# WirelessPowerRxExtensionBoard.net
KiCad netlist of a schematic drawn in EAGLE
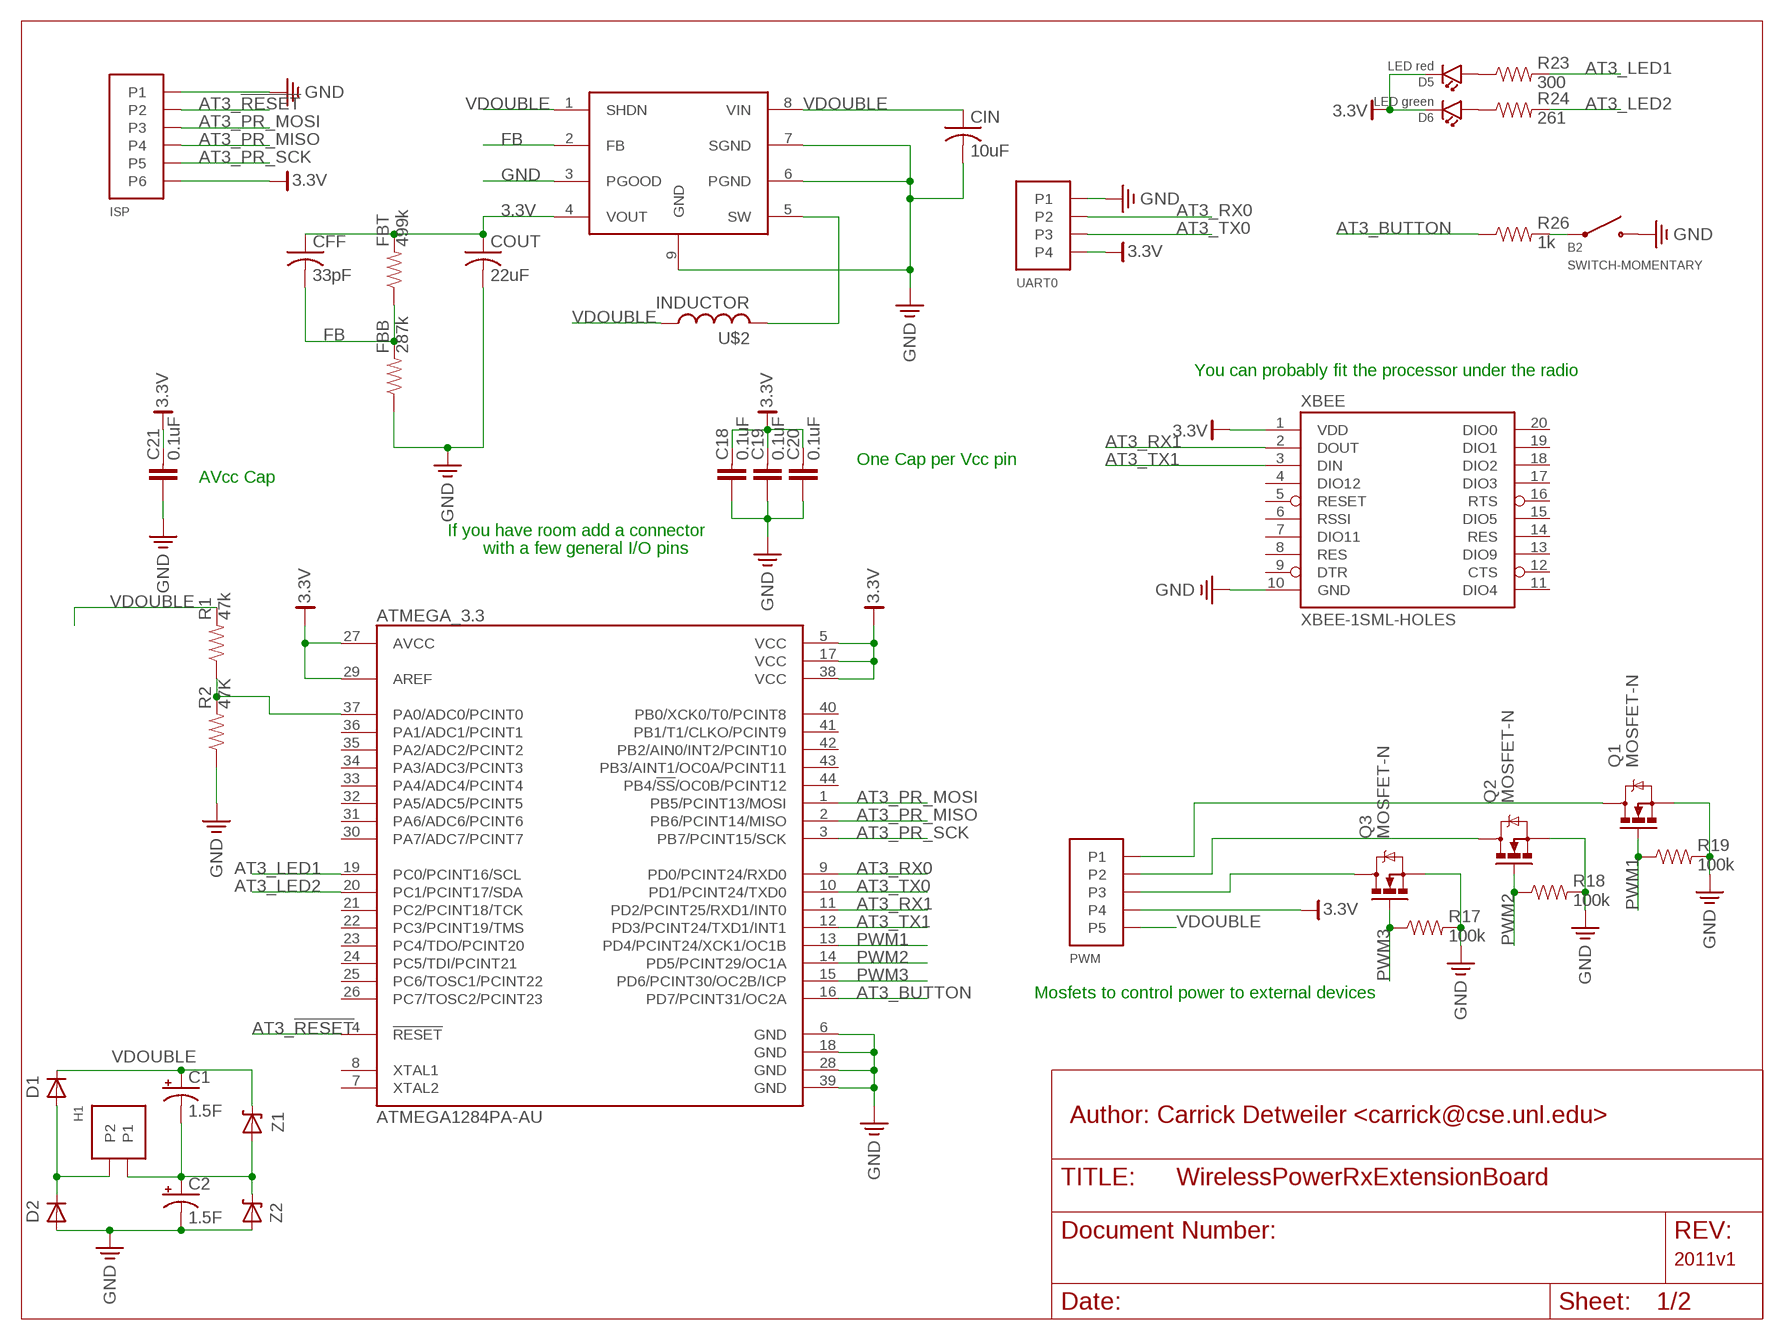
[diagram p0: schematic, sheet 1]
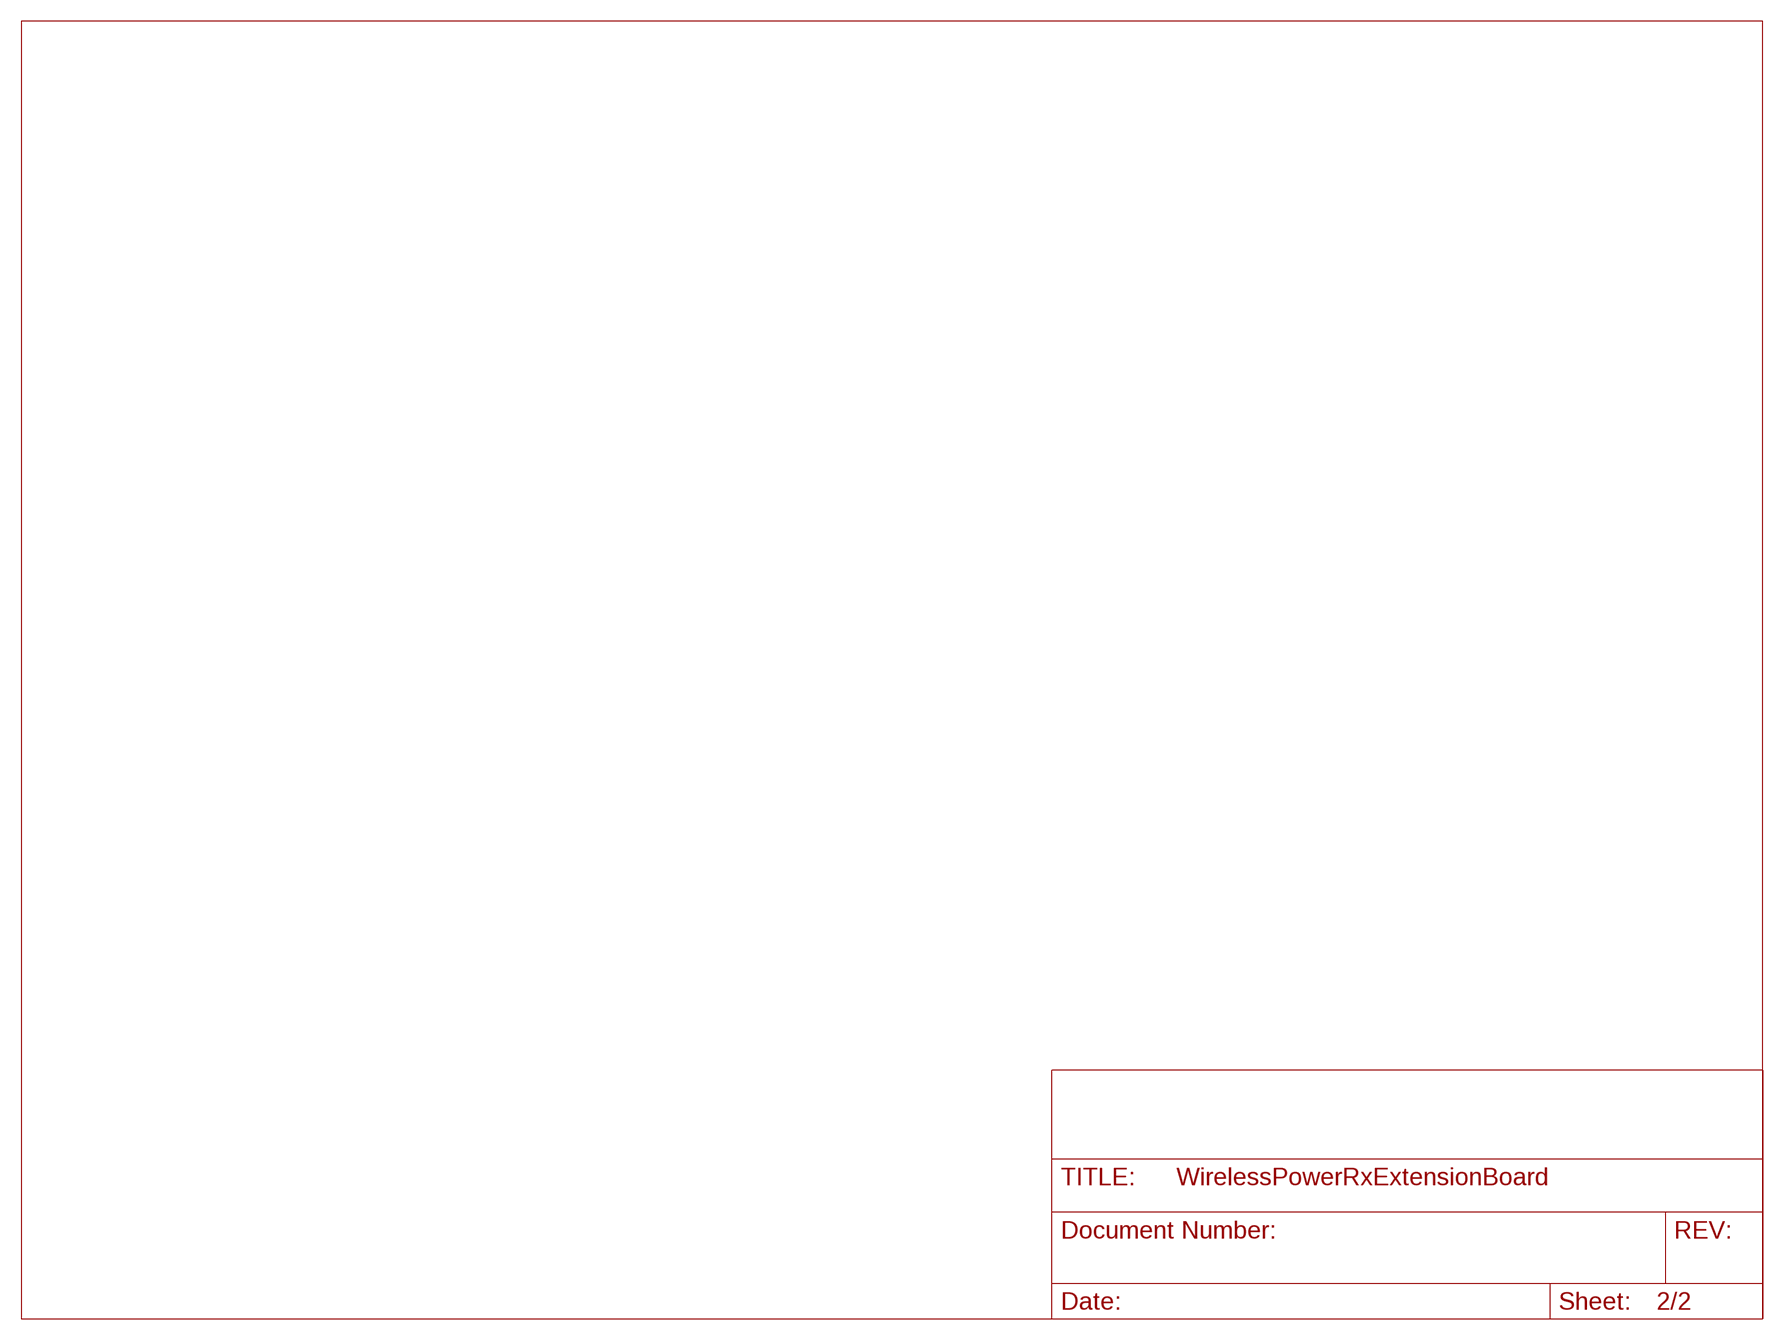
[diagram p1: schematic, sheet 2]

(export (version "E")
  (design (tool "Eeschema 10.0.6"))
  (components
    (comp (ref "ATMEGA_3.3")
      (value "ATMEGA1284PA-AU")
      (footprint "eagle-import:AT_TQFP-44")
      (libsource (lib "eagle-import") (part "ATMEGA164PA-AU"))
    )
    (comp (ref "B2")
      (value "SWITCH-MOMENTARY")
      (footprint "eagle-import:SWITCH-MOMENTARY-PTS635-SMD")
      (libsource (lib "eagle-import") (part "SWITCH-MOMENTARY"))
    )
    (comp (ref "C1")
      (value "1.5F")
      (footprint "eagle-import:E5-10,5")
      (libsource (lib "eagle-import") (part "CPOL-USE5-10.5"))
    )
    (comp (ref "C2")
      (value "1.5F")
      (footprint "eagle-import:E5-10,5")
      (libsource (lib "eagle-import") (part "CPOL-USE5-10.5"))
    )
    (comp (ref "C18")
      (value "0.1uF")
      (footprint "eagle-import:C0603")
      (libsource (lib "eagle-import") (part "CAP0603"))
    )
    (comp (ref "C19")
      (value "0.1uF")
      (footprint "eagle-import:C0603")
      (libsource (lib "eagle-import") (part "CAP0603"))
    )
    (comp (ref "C20")
      (value "0.1uF")
      (footprint "eagle-import:C0603")
      (libsource (lib "eagle-import") (part "CAP0603"))
    )
    (comp (ref "C21")
      (value "0.1uF")
      (footprint "eagle-import:C0603")
      (libsource (lib "eagle-import") (part "CAP0603"))
    )
    (comp (ref "CFF")
      (value "33pF")
      (footprint "eagle-import:C0201")
      (libsource (lib "eagle-import") (part "C-USC0201"))
    )
    (comp (ref "CIN")
      (value "10uF")
      (footprint "eagle-import:C0805")
      (libsource (lib "eagle-import") (part "C-USC0805"))
    )
    (comp (ref "COUT")
      (value "22uF")
      (footprint "eagle-import:C0805")
      (libsource (lib "eagle-import") (part "C-USC0805"))
    )
    (comp (ref "D1")
      (value "DIODE")
      (footprint "eagle-import:DO-214AB")
      (libsource (lib "eagle-import") (part "DIODE"))
    )
    (comp (ref "D2")
      (value "DIODE")
      (footprint "eagle-import:DO-214AB")
      (libsource (lib "eagle-import") (part "DIODE"))
    )
    (comp (ref "D5")
      (value "LED red")
      (footprint "eagle-import:LED0603")
      (libsource (lib "eagle-import") (part "LED"))
    )
    (comp (ref "D6")
      (value "LED green")
      (footprint "eagle-import:LED0603")
      (libsource (lib "eagle-import") (part "LED"))
    )
    (comp (ref "FBB")
      (value "287k")
      (footprint "eagle-import:R0603")
      (libsource (lib "eagle-import") (part "carrick_RES0603"))
    )
    (comp (ref "FBT")
      (value "499k")
      (footprint "eagle-import:R0603")
      (libsource (lib "eagle-import") (part "carrick_RES0603"))
    )
    (comp (ref "H1")
      (value "DF3-2")
      (footprint "eagle-import:DF3-2")
      (libsource (lib "eagle-import") (part "DF3-2"))
    )
    (comp (ref "ISP")
      (value "DF3-6")
      (footprint "eagle-import:DF3-6")
      (libsource (lib "eagle-import") (part "DF3-6"))
    )
    (comp (ref "PWM")
      (value "DF3-5")
      (footprint "eagle-import:DF3-5")
      (libsource (lib "eagle-import") (part "DF3-5"))
    )
    (comp (ref "Q1")
      (value "MOSFET-N")
      (footprint "eagle-import:SOT-23")
      (libsource (lib "eagle-import") (part "MOSFET-N"))
    )
    (comp (ref "Q2")
      (value "MOSFET-N")
      (footprint "eagle-import:SOT-23")
      (libsource (lib "eagle-import") (part "MOSFET-N"))
    )
    (comp (ref "Q3")
      (value "MOSFET-N")
      (footprint "eagle-import:SOT-23")
      (libsource (lib "eagle-import") (part "MOSFET-N"))
    )
    (comp (ref "R1")
      (value "47k")
      (footprint "eagle-import:R0603")
      (libsource (lib "eagle-import") (part "carrick_RES0603"))
    )
    (comp (ref "R2")
      (value "47K")
      (footprint "eagle-import:R0603")
      (libsource (lib "eagle-import") (part "carrick_RES0603"))
    )
    (comp (ref "R17")
      (value "100k")
      (footprint "eagle-import:R0603")
      (libsource (lib "eagle-import") (part "carrick_RES0603"))
    )
    (comp (ref "R18")
      (value "100k")
      (footprint "eagle-import:R0603")
      (libsource (lib "eagle-import") (part "carrick_RES0603"))
    )
    (comp (ref "R19")
      (value "100k")
      (footprint "eagle-import:R0603")
      (libsource (lib "eagle-import") (part "carrick_RES0603"))
    )
    (comp (ref "R23")
      (value "300")
      (footprint "eagle-import:R0603")
      (libsource (lib "eagle-import") (part "RES0603"))
    )
    (comp (ref "R24")
      (value "261")
      (footprint "eagle-import:R0603")
      (libsource (lib "eagle-import") (part "RES0603"))
    )
    (comp (ref "R26")
      (value "1k")
      (footprint "eagle-import:R0603")
      (libsource (lib "eagle-import") (part "RES0603"))
    )
    (comp (ref "U$1")
      (value "STEPUPCONVERTER")
      (footprint "eagle-import:LTC3528_LTC3528B")
      (libsource (lib "eagle-import") (part "STEPUPCONVERTER"))
    )
    (comp (ref "U$2")
      (value "INDUCTOR")
      (footprint "eagle-import:WE-TPC-M")
      (libsource (lib "eagle-import") (part "INDUCTOR"))
    )
    (comp (ref "UART0")
      (value "DF3-4")
      (footprint "eagle-import:DF3-4")
      (libsource (lib "eagle-import") (part "DF3-4"))
    )
    (comp (ref "XBEE")
      (value "XBEE-1SML-HOLES")
      (footprint "eagle-import:XBEE-SML-HOLES")
      (libsource (lib "eagle-import") (part "XBEE-1SML-HOLES"))
    )
    (comp (ref "Z1")
      (value "ZENERDIODE")
      (footprint "eagle-import:SOD-123")
      (libsource (lib "eagle-import") (part "ZENERDIODE"))
    )
    (comp (ref "Z2")
      (value "ZENERDIODE")
      (footprint "eagle-import:SOD-123")
      (libsource (lib "eagle-import") (part "ZENERDIODE"))
    )
  )
  (nets
    (net (code "1") (name "3.3V") (class "Default")
      (node (ref "ATMEGA_3.3") (pin "17") (pinfunction "VCC_17") (pintype "power_in"))
      (node (ref "ATMEGA_3.3") (pin "27") (pinfunction "AVCC_27") (pintype "power_in"))
      (node (ref "ATMEGA_3.3") (pin "29") (pinfunction "AREF_29") (pintype "passive"))
      (node (ref "ATMEGA_3.3") (pin "38") (pinfunction "VCC_38") (pintype "power_in"))
      (node (ref "ATMEGA_3.3") (pin "5") (pinfunction "VCC_5") (pintype "power_in"))
      (node (ref "C18") (pin "P$2") (pinfunction "P$2_P$2") (pintype "bidirectional"))
      (node (ref "C19") (pin "P$2") (pinfunction "P$2_P$2") (pintype "bidirectional"))
      (node (ref "C20") (pin "P$2") (pinfunction "P$2_P$2") (pintype "bidirectional"))
      (node (ref "C21") (pin "P$2") (pinfunction "P$2_P$2") (pintype "bidirectional"))
      (node (ref "CFF") (pin "1") (pinfunction "1_1") (pintype "passive"))
      (node (ref "COUT") (pin "1") (pinfunction "1_1") (pintype "passive"))
      (node (ref "D5") (pin "P$2") (pinfunction "P$2_P$2") (pintype "bidirectional"))
      (node (ref "D6") (pin "P$2") (pinfunction "P$2_P$2") (pintype "bidirectional"))
      (node (ref "FBT") (pin "P$2") (pinfunction "2_P$2") (pintype "passive"))
      (node (ref "ISP") (pin "P$6") (pinfunction "P6_P$6") (pintype "bidirectional"))
      (node (ref "PWM") (pin "P$4") (pinfunction "P4_P$4") (pintype "bidirectional"))
      (node (ref "U$1") (pin "4") (pinfunction "VOUT_4") (pintype "power_in"))
      (node (ref "UART0") (pin "P$4") (pinfunction "P4_P$4") (pintype "bidirectional"))
      (node (ref "XBEE") (pin "1") (pinfunction "VDD_1") (pintype "power_in"))
    )
    (net (code "2") (name "AT3_BUTTON") (class "Default")
      (node (ref "ATMEGA_3.3") (pin "16") (pinfunction "PD7/PCINT31/OC2A_16") (pintype "bidirectional"))
      (node (ref "R26") (pin "P$1") (pinfunction "1_P$1") (pintype "passive"))
    )
    (net (code "3") (name "AT3_LED1") (class "Default")
      (node (ref "ATMEGA_3.3") (pin "19") (pinfunction "PC0/PCINT16/SCL_19") (pintype "bidirectional"))
      (node (ref "R23") (pin "P$2") (pinfunction "2_P$2") (pintype "passive"))
    )
    (net (code "4") (name "AT3_LED2") (class "Default")
      (node (ref "ATMEGA_3.3") (pin "20") (pinfunction "PC1/PCINT17/SDA_20") (pintype "bidirectional"))
      (node (ref "R24") (pin "P$2") (pinfunction "2_P$2") (pintype "passive"))
    )
    (net (code "5") (name "AT3_PR_MISO") (class "Default")
      (node (ref "ATMEGA_3.3") (pin "2") (pinfunction "PB6/PCINT14/MISO_2") (pintype "bidirectional"))
      (node (ref "ISP") (pin "P$4") (pinfunction "P4_P$4") (pintype "bidirectional"))
    )
    (net (code "6") (name "AT3_PR_MOSI") (class "Default")
      (node (ref "ATMEGA_3.3") (pin "1") (pinfunction "PB5/PCINT13/MOSI_1") (pintype "bidirectional"))
      (node (ref "ISP") (pin "P$3") (pinfunction "P3_P$3") (pintype "bidirectional"))
    )
    (net (code "7") (name "AT3_PR_SCK") (class "Default")
      (node (ref "ATMEGA_3.3") (pin "3") (pinfunction "PB7/PCINT15/SCK_3") (pintype "bidirectional"))
      (node (ref "ISP") (pin "P$5") (pinfunction "P5_P$5") (pintype "bidirectional"))
    )
    (net (code "8") (name "AT3_RX0") (class "Default")
      (node (ref "ATMEGA_3.3") (pin "9") (pinfunction "PD0/PCINT24/RXD0_9") (pintype "bidirectional"))
      (node (ref "UART0") (pin "P$2") (pinfunction "P2_P$2") (pintype "bidirectional"))
    )
    (net (code "9") (name "AT3_RX1") (class "Default")
      (node (ref "ATMEGA_3.3") (pin "11") (pinfunction "PD2/PCINT25/RXD1/INT0_11") (pintype "bidirectional"))
      (node (ref "XBEE") (pin "2") (pinfunction "DOUT_2") (pintype "output"))
    )
    (net (code "10") (name "AT3_TX0") (class "Default")
      (node (ref "ATMEGA_3.3") (pin "10") (pinfunction "PD1/PCINT24/TXD0_10") (pintype "bidirectional"))
      (node (ref "UART0") (pin "P$3") (pinfunction "P3_P$3") (pintype "bidirectional"))
    )
    (net (code "11") (name "AT3_TX1") (class "Default")
      (node (ref "ATMEGA_3.3") (pin "12") (pinfunction "PD3/PCINT24/TXD1/INT1_12") (pintype "bidirectional"))
      (node (ref "XBEE") (pin "3") (pinfunction "DIN_3") (pintype "input"))
    )
    (net (code "12") (name "AT3_~{RESET}") (class "Default")
      (node (ref "ATMEGA_3.3") (pin "4") (pinfunction "~{RESET}_4") (pintype "input"))
      (node (ref "ISP") (pin "P$2") (pinfunction "P2_P$2") (pintype "bidirectional"))
    )
    (net (code "13") (name "FB") (class "Default")
      (node (ref "CFF") (pin "2") (pinfunction "2_2") (pintype "passive"))
      (node (ref "FBB") (pin "P$2") (pinfunction "2_P$2") (pintype "passive"))
      (node (ref "FBT") (pin "P$1") (pinfunction "1_P$1") (pintype "passive"))
      (node (ref "U$1") (pin "2") (pinfunction "FB_2") (pintype "bidirectional"))
    )
    (net (code "14") (name "GND") (class "Default")
      (node (ref "ATMEGA_3.3") (pin "18") (pinfunction "GND_18") (pintype "power_in"))
      (node (ref "ATMEGA_3.3") (pin "28") (pinfunction "GND_28") (pintype "power_in"))
      (node (ref "ATMEGA_3.3") (pin "39") (pinfunction "GND_39") (pintype "power_in"))
      (node (ref "ATMEGA_3.3") (pin "6") (pinfunction "GND_6") (pintype "power_in"))
      (node (ref "B2") (pin "P$2") (pinfunction "P$2_P$2") (pintype "bidirectional"))
      (node (ref "C18") (pin "P$1") (pinfunction "P$1_P$1") (pintype "bidirectional"))
      (node (ref "C19") (pin "P$1") (pinfunction "P$1_P$1") (pintype "bidirectional"))
      (node (ref "C2") (pin "-") (pinfunction "-_-") (pintype "passive"))
      (node (ref "C20") (pin "P$1") (pinfunction "P$1_P$1") (pintype "bidirectional"))
      (node (ref "C21") (pin "P$1") (pinfunction "P$1_P$1") (pintype "bidirectional"))
      (node (ref "CIN") (pin "2") (pinfunction "2_2") (pintype "passive"))
      (node (ref "COUT") (pin "2") (pinfunction "2_2") (pintype "passive"))
      (node (ref "D2") (pin "P$2") (pinfunction "A_P$2") (pintype "passive"))
      (node (ref "FBB") (pin "P$1") (pinfunction "1_P$1") (pintype "passive"))
      (node (ref "ISP") (pin "P$1") (pinfunction "P1_P$1") (pintype "bidirectional"))
      (node (ref "Q1") (pin "2") (pinfunction "S_2") (pintype "passive"))
      (node (ref "Q2") (pin "2") (pinfunction "S_2") (pintype "passive"))
      (node (ref "Q3") (pin "2") (pinfunction "S_2") (pintype "passive"))
      (node (ref "R17") (pin "P$2") (pinfunction "2_P$2") (pintype "passive"))
      (node (ref "R18") (pin "P$2") (pinfunction "2_P$2") (pintype "passive"))
      (node (ref "R19") (pin "P$2") (pinfunction "2_P$2") (pintype "passive"))
      (node (ref "R2") (pin "P$1") (pinfunction "1_P$1") (pintype "passive"))
      (node (ref "U$1") (pin "3") (pinfunction "PGOOD_3") (pintype "bidirectional"))
      (node (ref "U$1") (pin "6") (pinfunction "PGND_6") (pintype "bidirectional"))
      (node (ref "U$1") (pin "7") (pinfunction "SGND_7") (pintype "bidirectional"))
      (node (ref "U$1") (pin "9") (pinfunction "GND_9") (pintype "power_in"))
      (node (ref "UART0") (pin "P$1") (pinfunction "P1_P$1") (pintype "bidirectional"))
      (node (ref "XBEE") (pin "10") (pinfunction "GND_10") (pintype "power_in"))
      (node (ref "Z2") (pin "P$2") (pinfunction "A_P$2") (pintype "passive"))
    )
    (net (code "15") (name "Net-(ATMEGA_3.3-PA0{slash}ADC0{slash}PCINT0)") (class "Default")
      (node (ref "ATMEGA_3.3") (pin "37") (pinfunction "PA0/ADC0/PCINT0_37") (pintype "bidirectional"))
      (node (ref "R1") (pin "P$1") (pinfunction "1_P$1") (pintype "passive"))
      (node (ref "R2") (pin "P$2") (pinfunction "2_P$2") (pintype "passive"))
    )
    (net (code "16") (name "Net-(D1-A)") (class "Default")
      (node (ref "D1") (pin "P$2") (pinfunction "A_P$2") (pintype "passive"))
      (node (ref "D2") (pin "P$1") (pinfunction "C_P$1") (pintype "passive"))
      (node (ref "H1") (pin "P$2") (pinfunction "P2_P$2") (pintype "bidirectional"))
    )
    (net (code "17") (name "Net-(H1-P1)") (class "Default")
      (node (ref "C1") (pin "-") (pinfunction "-_-") (pintype "passive"))
      (node (ref "C2") (pin "+") (pinfunction "+_+") (pintype "passive"))
      (node (ref "H1") (pin "P$1") (pinfunction "P1_P$1") (pintype "bidirectional"))
      (node (ref "Z1") (pin "P$2") (pinfunction "A_P$2") (pintype "passive"))
      (node (ref "Z2") (pin "P$1") (pinfunction "C_P$1") (pintype "passive"))
    )
    (net (code "18") (name "Net-(PWM-P1)") (class "Default")
      (node (ref "PWM") (pin "P$1") (pinfunction "P1_P$1") (pintype "bidirectional"))
      (node (ref "Q1") (pin "3") (pinfunction "D_3") (pintype "passive"))
    )
    (net (code "19") (name "Net-(PWM-P2)") (class "Default")
      (node (ref "PWM") (pin "P$2") (pinfunction "P2_P$2") (pintype "bidirectional"))
      (node (ref "Q2") (pin "3") (pinfunction "D_3") (pintype "passive"))
    )
    (net (code "20") (name "Net-(PWM-P3)") (class "Default")
      (node (ref "PWM") (pin "P$3") (pinfunction "P3_P$3") (pintype "bidirectional"))
      (node (ref "Q3") (pin "3") (pinfunction "D_3") (pintype "passive"))
    )
    (net (code "21") (name "Net-(R23-1)") (class "Default")
      (node (ref "D5") (pin "P$1") (pinfunction "P$1_P$1") (pintype "bidirectional"))
      (node (ref "R23") (pin "P$1") (pinfunction "1_P$1") (pintype "passive"))
    )
    (net (code "22") (name "Net-(R24-1)") (class "Default")
      (node (ref "D6") (pin "P$1") (pinfunction "P$1_P$1") (pintype "bidirectional"))
      (node (ref "R24") (pin "P$1") (pinfunction "1_P$1") (pintype "passive"))
    )
    (net (code "23") (name "Net-(R26-2)") (class "Default")
      (node (ref "B2") (pin "P$1") (pinfunction "P$1_P$1") (pintype "bidirectional"))
      (node (ref "R26") (pin "P$2") (pinfunction "2_P$2") (pintype "passive"))
    )
    (net (code "24") (name "Net-(U$1-SW)") (class "Default")
      (node (ref "U$1") (pin "5") (pinfunction "SW_5") (pintype "bidirectional"))
      (node (ref "U$2") (pin "P$2") (pinfunction "2_P$2") (pintype "passive"))
    )
    (net (code "25") (name "PWM1") (class "Default")
      (node (ref "ATMEGA_3.3") (pin "13") (pinfunction "PD4/PCINT24/XCK1/OC1B_13") (pintype "bidirectional"))
      (node (ref "Q1") (pin "1") (pinfunction "G_1") (pintype "passive"))
      (node (ref "R19") (pin "P$1") (pinfunction "1_P$1") (pintype "passive"))
    )
    (net (code "26") (name "PWM2") (class "Default")
      (node (ref "ATMEGA_3.3") (pin "14") (pinfunction "PD5/PCINT29/OC1A_14") (pintype "bidirectional"))
      (node (ref "Q2") (pin "1") (pinfunction "G_1") (pintype "passive"))
      (node (ref "R18") (pin "P$1") (pinfunction "1_P$1") (pintype "passive"))
    )
    (net (code "27") (name "PWM3") (class "Default")
      (node (ref "ATMEGA_3.3") (pin "15") (pinfunction "PD6/PCINT30/OC2B/ICP_15") (pintype "bidirectional"))
      (node (ref "Q3") (pin "1") (pinfunction "G_1") (pintype "passive"))
      (node (ref "R17") (pin "P$1") (pinfunction "1_P$1") (pintype "passive"))
    )
    (net (code "28") (name "VDOUBLE") (class "Default")
      (node (ref "C1") (pin "+") (pinfunction "+_+") (pintype "passive"))
      (node (ref "CIN") (pin "1") (pinfunction "1_1") (pintype "passive"))
      (node (ref "D1") (pin "P$1") (pinfunction "C_P$1") (pintype "passive"))
      (node (ref "PWM") (pin "P$5") (pinfunction "P5_P$5") (pintype "bidirectional"))
      (node (ref "R1") (pin "P$2") (pinfunction "2_P$2") (pintype "passive"))
      (node (ref "U$1") (pin "1") (pinfunction "SHDN_1") (pintype "input"))
      (node (ref "U$1") (pin "8") (pinfunction "VIN_8") (pintype "input"))
      (node (ref "U$2") (pin "P$1") (pinfunction "1_P$1") (pintype "passive"))
      (node (ref "Z1") (pin "P$1") (pinfunction "C_P$1") (pintype "passive"))
    )
    (net (code "29") (name "unconnected-(ATMEGA_3.3-PA1{slash}ADC1{slash}PCINT1-Pad36)") (class "Default")
      (node (ref "ATMEGA_3.3") (pin "36") (pinfunction "PA1/ADC1/PCINT1_36") (pintype "bidirectional"))
    )
    (net (code "30") (name "unconnected-(ATMEGA_3.3-PA2{slash}ADC2{slash}PCINT2-Pad35)") (class "Default")
      (node (ref "ATMEGA_3.3") (pin "35") (pinfunction "PA2/ADC2/PCINT2_35") (pintype "bidirectional"))
    )
    (net (code "31") (name "unconnected-(ATMEGA_3.3-PA3{slash}ADC3{slash}PCINT3-Pad34)") (class "Default")
      (node (ref "ATMEGA_3.3") (pin "34") (pinfunction "PA3/ADC3/PCINT3_34") (pintype "bidirectional"))
    )
    (net (code "32") (name "unconnected-(ATMEGA_3.3-PA4{slash}ADC4{slash}PCINT4-Pad33)") (class "Default")
      (node (ref "ATMEGA_3.3") (pin "33") (pinfunction "PA4/ADC4/PCINT4_33") (pintype "bidirectional"))
    )
    (net (code "33") (name "unconnected-(ATMEGA_3.3-PA5{slash}ADC5{slash}PCINT5-Pad32)") (class "Default")
      (node (ref "ATMEGA_3.3") (pin "32") (pinfunction "PA5/ADC5/PCINT5_32") (pintype "bidirectional"))
    )
    (net (code "34") (name "unconnected-(ATMEGA_3.3-PA6{slash}ADC6{slash}PCINT6-Pad31)") (class "Default")
      (node (ref "ATMEGA_3.3") (pin "31") (pinfunction "PA6/ADC6/PCINT6_31") (pintype "bidirectional"))
    )
    (net (code "35") (name "unconnected-(ATMEGA_3.3-PA7{slash}ADC7{slash}PCINT7-Pad30)") (class "Default")
      (node (ref "ATMEGA_3.3") (pin "30") (pinfunction "PA7/ADC7/PCINT7_30") (pintype "bidirectional"))
    )
    (net (code "36") (name "unconnected-(ATMEGA_3.3-PB0{slash}XCK0{slash}T0{slash}PCINT8-Pad40)") (class "Default")
      (node (ref "ATMEGA_3.3") (pin "40") (pinfunction "PB0/XCK0/T0/PCINT8_40") (pintype "bidirectional"))
    )
    (net (code "37") (name "unconnected-(ATMEGA_3.3-PB1{slash}T1{slash}CLKO{slash}PCINT9-Pad41)") (class "Default")
      (node (ref "ATMEGA_3.3") (pin "41") (pinfunction "PB1/T1/CLKO/PCINT9_41") (pintype "bidirectional"))
    )
    (net (code "38") (name "unconnected-(ATMEGA_3.3-PB2{slash}AIN0{slash}INT2{slash}PCINT10-Pad42)") (class "Default")
      (node (ref "ATMEGA_3.3") (pin "42") (pinfunction "PB2/AIN0/INT2/PCINT10_42") (pintype "bidirectional"))
    )
    (net (code "39") (name "unconnected-(ATMEGA_3.3-PB3{slash}AINT1{slash}OC0A{slash}PCINT11-Pad43)") (class "Default")
      (node (ref "ATMEGA_3.3") (pin "43") (pinfunction "PB3/AINT1/OC0A/PCINT11_43") (pintype "bidirectional"))
    )
    (net (code "40") (name "unconnected-(ATMEGA_3.3-PB4{slash}~{SS}{slash}OC0B{slash}PCINT12-Pad44)") (class "Default")
      (node (ref "ATMEGA_3.3") (pin "44") (pinfunction "PB4/~{SS}/OC0B/PCINT12_44") (pintype "bidirectional"))
    )
    (net (code "41") (name "unconnected-(ATMEGA_3.3-PC2{slash}PCINT18{slash}TCK-Pad21)") (class "Default")
      (node (ref "ATMEGA_3.3") (pin "21") (pinfunction "PC2/PCINT18/TCK_21") (pintype "bidirectional"))
    )
    (net (code "42") (name "unconnected-(ATMEGA_3.3-PC3{slash}PCINT19{slash}TMS-Pad22)") (class "Default")
      (node (ref "ATMEGA_3.3") (pin "22") (pinfunction "PC3/PCINT19/TMS_22") (pintype "bidirectional"))
    )
    (net (code "43") (name "unconnected-(ATMEGA_3.3-PC4{slash}TDO{slash}PCINT20-Pad23)") (class "Default")
      (node (ref "ATMEGA_3.3") (pin "23") (pinfunction "PC4/TDO/PCINT20_23") (pintype "bidirectional"))
    )
    (net (code "44") (name "unconnected-(ATMEGA_3.3-PC5{slash}TDI{slash}PCINT21-Pad24)") (class "Default")
      (node (ref "ATMEGA_3.3") (pin "24") (pinfunction "PC5/TDI/PCINT21_24") (pintype "bidirectional"))
    )
    (net (code "45") (name "unconnected-(ATMEGA_3.3-PC6{slash}TOSC1{slash}PCINT22-Pad25)") (class "Default")
      (node (ref "ATMEGA_3.3") (pin "25") (pinfunction "PC6/TOSC1/PCINT22_25") (pintype "bidirectional"))
    )
    (net (code "46") (name "unconnected-(ATMEGA_3.3-PC7{slash}TOSC2{slash}PCINT23-Pad26)") (class "Default")
      (node (ref "ATMEGA_3.3") (pin "26") (pinfunction "PC7/TOSC2/PCINT23_26") (pintype "bidirectional"))
    )
    (net (code "47") (name "unconnected-(ATMEGA_3.3-XTAL1-Pad8)") (class "Default")
      (node (ref "ATMEGA_3.3") (pin "8") (pinfunction "XTAL1_8") (pintype "passive"))
    )
    (net (code "48") (name "unconnected-(ATMEGA_3.3-XTAL2-Pad7)") (class "Default")
      (node (ref "ATMEGA_3.3") (pin "7") (pinfunction "XTAL2_7") (pintype "passive"))
    )
    (net (code "49") (name "unconnected-(XBEE-CTS-Pad12)") (class "Default")
      (node (ref "XBEE") (pin "12") (pinfunction "CTS_12") (pintype "output"))
    )
    (net (code "50") (name "unconnected-(XBEE-DIO0-Pad20)") (class "Default")
      (node (ref "XBEE") (pin "20") (pinfunction "DIO0_20") (pintype "bidirectional"))
    )
    (net (code "51") (name "unconnected-(XBEE-DIO1-Pad19)") (class "Default")
      (node (ref "XBEE") (pin "19") (pinfunction "DIO1_19") (pintype "bidirectional"))
    )
    (net (code "52") (name "unconnected-(XBEE-DIO2-Pad18)") (class "Default")
      (node (ref "XBEE") (pin "18") (pinfunction "DIO2_18") (pintype "bidirectional"))
    )
    (net (code "53") (name "unconnected-(XBEE-DIO3-Pad17)") (class "Default")
      (node (ref "XBEE") (pin "17") (pinfunction "DIO3_17") (pintype "bidirectional"))
    )
    (net (code "54") (name "unconnected-(XBEE-DIO4-Pad11)") (class "Default")
      (node (ref "XBEE") (pin "11") (pinfunction "DIO4_11") (pintype "bidirectional"))
    )
    (net (code "55") (name "unconnected-(XBEE-DIO5-Pad15)") (class "Default")
      (node (ref "XBEE") (pin "15") (pinfunction "DIO5_15") (pintype "bidirectional"))
    )
    (net (code "56") (name "unconnected-(XBEE-DIO9-Pad13)") (class "Default")
      (node (ref "XBEE") (pin "13") (pinfunction "DIO9_13") (pintype "bidirectional"))
    )
    (net (code "57") (name "unconnected-(XBEE-DIO11-Pad7)") (class "Default")
      (node (ref "XBEE") (pin "7") (pinfunction "DIO11_7") (pintype "bidirectional"))
    )
    (net (code "58") (name "unconnected-(XBEE-DIO12-Pad4)") (class "Default")
      (node (ref "XBEE") (pin "4") (pinfunction "DIO12_4") (pintype "bidirectional"))
    )
    (net (code "59") (name "unconnected-(XBEE-DTR-Pad9)") (class "Default")
      (node (ref "XBEE") (pin "9") (pinfunction "DTR_9") (pintype "bidirectional"))
    )
    (net (code "60") (name "unconnected-(XBEE-RES-Pad8)") (class "Default")
      (node (ref "XBEE") (pin "8") (pinfunction "RES_8") (pintype "bidirectional"))
    )
    (net (code "61") (name "unconnected-(XBEE-RES-Pad14)") (class "Default")
      (node (ref "XBEE") (pin "14") (pinfunction "RES_14") (pintype "bidirectional"))
    )
    (net (code "62") (name "unconnected-(XBEE-RESET-Pad5)") (class "Default")
      (node (ref "XBEE") (pin "5") (pinfunction "RESET_5") (pintype "input"))
    )
    (net (code "63") (name "unconnected-(XBEE-RSSI-Pad6)") (class "Default")
      (node (ref "XBEE") (pin "6") (pinfunction "RSSI_6") (pintype "bidirectional"))
    )
    (net (code "64") (name "unconnected-(XBEE-RTS-Pad16)") (class "Default")
      (node (ref "XBEE") (pin "16") (pinfunction "RTS_16") (pintype "input"))
    )
  )
)
